# RS485.net
KiCad netlist of a schematic drawn in Altium Designer
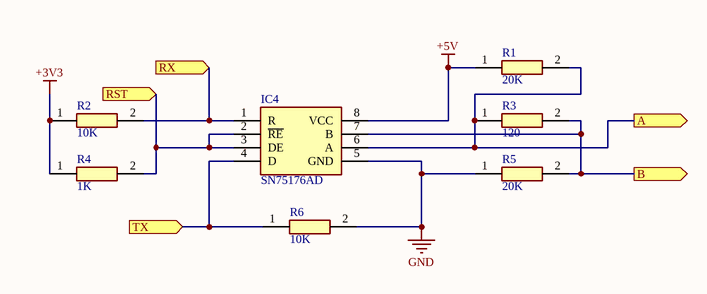
[diagram p0: RS485.SchDoc]

(export (version "E")
  (design (tool "Eeschema 10.0.6"))
  (components
    (comp (ref "IC4")
      (value "SN75176AD")
      (footprint "SamacSys:SOIC127P600X175-8N")
      (description "Integrated Circuit")
      (fields (field (name "MOUSER PART NUMBER") "595-SN75176AD"))
      (libsource (lib "*") (part "SN75176AD"))
    )
    (comp (ref "R1")
      (value "20K")
      (footprint "SamacSys:RESC3216X75N")
      (description "Resistor")
      (fields
        (field (name "MANUFACTURER_PART_NUMBER") "CR1206-F/-2R00ELF")
        (field (name "MOUSER PART NUMBER") "652-CR1206-F/2R00ELF")
      )
      (libsource (lib "*") (part "CR1206-F_-2R00ELF"))
    )
    (comp (ref "R2")
      (value "10K")
      (footprint "SamacSys:RESC3216X75N")
      (description "Resistor")
      (fields
        (field (name "MANUFACTURER_PART_NUMBER") "CR1206-F/-2R00ELF")
        (field (name "MOUSER PART NUMBER") "652-CR1206-F/2R00ELF")
      )
      (libsource (lib "*") (part "CR1206-F_-2R00ELF"))
    )
    (comp (ref "R3")
      (value "120")
      (footprint "SamacSys:RESC3216X75N")
      (description "Resistor")
      (fields
        (field (name "MANUFACTURER_PART_NUMBER") "CR1206-F/-2R00ELF")
        (field (name "MOUSER PART NUMBER") "652-CR1206-F/2R00ELF")
      )
      (libsource (lib "*") (part "CR1206-F_-2R00ELF"))
    )
    (comp (ref "R4")
      (value "1K")
      (footprint "SamacSys:RESC3216X75N")
      (description "Resistor")
      (fields
        (field (name "MANUFACTURER_PART_NUMBER") "CR1206-F/-2R00ELF")
        (field (name "MOUSER PART NUMBER") "652-CR1206-F/2R00ELF")
      )
      (libsource (lib "*") (part "CR1206-F_-2R00ELF"))
    )
    (comp (ref "R5")
      (value "20K")
      (footprint "SamacSys:RESC3216X75N")
      (description "Resistor")
      (fields
        (field (name "MANUFACTURER_PART_NUMBER") "CR1206-F/-2R00ELF")
        (field (name "MOUSER PART NUMBER") "652-CR1206-F/2R00ELF")
      )
      (libsource (lib "*") (part "CR1206-F_-2R00ELF"))
    )
    (comp (ref "R6")
      (value "10K")
      (footprint "SamacSys:RESC3216X75N")
      (description "Resistor")
      (fields
        (field (name "MANUFACTURER_PART_NUMBER") "CR1206-F/-2R00ELF")
        (field (name "MOUSER PART NUMBER") "652-CR1206-F/2R00ELF")
      )
      (libsource (lib "*") (part "CR1206-F_-2R00ELF"))
    )
  )
  (nets
    (net (code "1") (name "+3V3") (class "Default")
      (node (ref "R2") (pin "1") (pinfunction "1_1") (pintype "passive"))
      (node (ref "R4") (pin "1") (pinfunction "1_1") (pintype "passive"))
    )
    (net (code "2") (name "+5V") (class "Default")
      (node (ref "IC4") (pin "8") (pinfunction "VCC_8") (pintype "passive"))
      (node (ref "R1") (pin "1") (pinfunction "1_1") (pintype "passive"))
    )
    (net (code "3") (name "/A") (class "Default")
      (node (ref "IC4") (pin "6") (pinfunction "A_6") (pintype "passive"))
      (node (ref "R1") (pin "2") (pinfunction "2_2") (pintype "passive"))
      (node (ref "R3") (pin "1") (pinfunction "1_1") (pintype "passive"))
    )
    (net (code "4") (name "/B") (class "Default")
      (node (ref "IC4") (pin "7") (pinfunction "B_7") (pintype "passive"))
      (node (ref "R3") (pin "2") (pinfunction "2_2") (pintype "passive"))
      (node (ref "R5") (pin "2") (pinfunction "2_2") (pintype "passive"))
    )
    (net (code "5") (name "/RST") (class "Default")
      (node (ref "IC4") (pin "2") (pinfunction "~{RE}_2") (pintype "passive"))
      (node (ref "IC4") (pin "3") (pinfunction "DE_3") (pintype "passive"))
      (node (ref "R4") (pin "2") (pinfunction "2_2") (pintype "passive"))
    )
    (net (code "6") (name "/RX") (class "Default")
      (node (ref "IC4") (pin "1") (pinfunction "R_1") (pintype "passive"))
      (node (ref "R2") (pin "2") (pinfunction "2_2") (pintype "passive"))
    )
    (net (code "7") (name "/TX") (class "Default")
      (node (ref "IC4") (pin "4") (pinfunction "D_4") (pintype "passive"))
      (node (ref "R6") (pin "1") (pinfunction "1_1") (pintype "passive"))
    )
    (net (code "8") (name "GND") (class "Default")
      (node (ref "IC4") (pin "5") (pinfunction "GND_5") (pintype "passive"))
      (node (ref "R5") (pin "1") (pinfunction "1_1") (pintype "passive"))
      (node (ref "R6") (pin "2") (pinfunction "2_2") (pintype "passive"))
    )
  )
)
